# design.net
KiCad netlist of a schematic drawn in Altium Designer
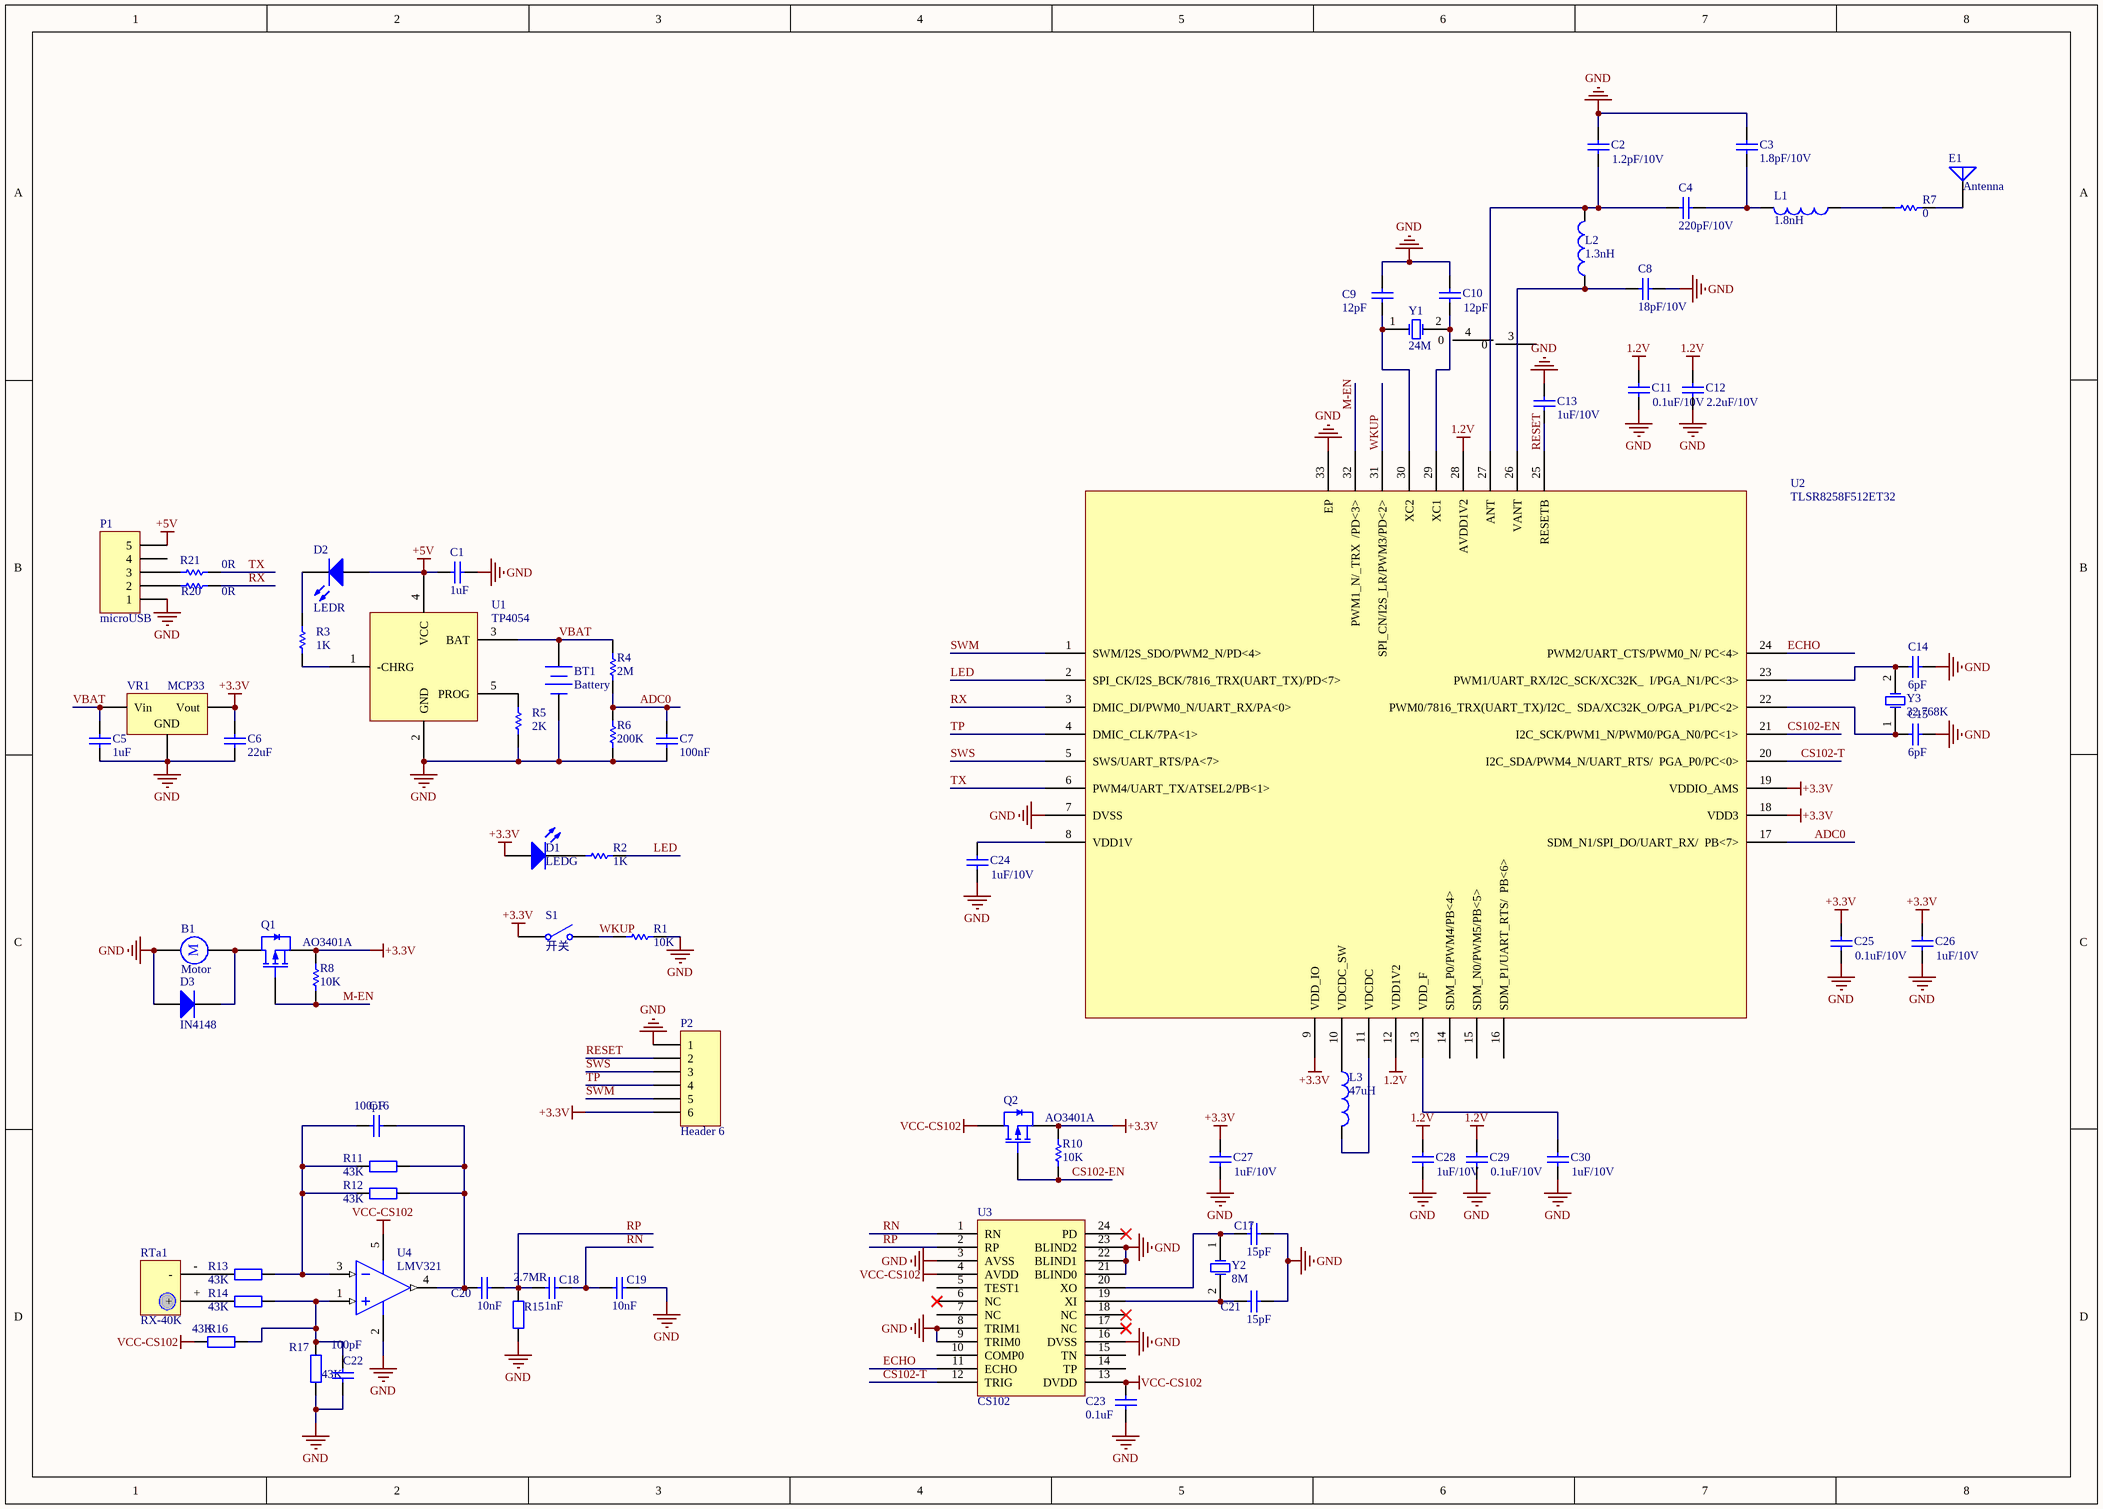
[diagram p0: 接收端原理图.SchDoc]

(export (version "E")
  (design (tool "Eeschema 10.0.6"))
  (components
    (comp (ref "B1")
      (value "Motor")
      (footprint "MOTO-40*44*114 - 3D")
      (description "Motor, General Kind")
      (fields (field (name "PUBLISHER") "Altium Limited"))
      (libsource (lib "Miscellaneous Devices") (part "Motor"))
    )
    (comp (ref "BT1")
      (value "Battery")
      (footprint "BT")
      (description "Multicell Battery")
      (fields (field (name "PUBLISHER") "Altium Limited"))
      (libsource (lib "Miscellaneous Devices") (part "Battery"))
    )
    (comp (ref "C1")
      (value "1uF")
      (description "Capacitor")
      (fields (field (name "PUBLISHER") "Altium Limited"))
      (libsource (lib "Miscellaneous Devices") (part "Cap"))
    )
    (comp (ref "C2")
      (value "1.2pF/10V")
      (footprint "0402")
      (description "Capacitor")
      (fields (field (name "PUBLISHER") "Altium Limited"))
      (libsource (lib "Miscellaneous Devices") (part "Cap"))
    )
    (comp (ref "C3")
      (value "1.8pF/10V")
      (footprint "0402")
      (description "Capacitor")
      (fields (field (name "PUBLISHER") "Altium Limited"))
      (libsource (lib "Miscellaneous Devices") (part "Cap"))
    )
    (comp (ref "C4")
      (value "220pF/10V")
      (footprint "0402")
      (description "Capacitor")
      (fields (field (name "PUBLISHER") "Altium Limited"))
      (libsource (lib "Miscellaneous Devices") (part "Cap"))
    )
    (comp (ref "C5")
      (value "1uF")
      (description "Capacitor")
      (fields (field (name "PUBLISHER") "Altium Limited"))
      (libsource (lib "Miscellaneous Devices") (part "Cap"))
    )
    (comp (ref "C6")
      (value "22uF")
      (description "Capacitor")
      (fields (field (name "PUBLISHER") "Altium Limited"))
      (libsource (lib "Miscellaneous Devices") (part "Cap"))
    )
    (comp (ref "C7")
      (value "100nF")
      (description "Capacitor")
      (fields (field (name "PUBLISHER") "Altium Limited"))
      (libsource (lib "Miscellaneous Devices") (part "Cap"))
    )
    (comp (ref "C8")
      (value "18pF/10V")
      (footprint "0402")
      (description "Capacitor")
      (fields (field (name "PUBLISHER") "Altium Limited"))
      (libsource (lib "Miscellaneous Devices") (part "Cap"))
    )
    (comp (ref "C9")
      (value "12pF")
      (footprint "0402")
      (description "Capacitor")
      (fields (field (name "PUBLISHER") "Altium Limited"))
      (libsource (lib "Miscellaneous Devices") (part "Cap"))
    )
    (comp (ref "C10")
      (value "12pF")
      (footprint "0402")
      (description "Capacitor")
      (fields (field (name "PUBLISHER") "Altium Limited"))
      (libsource (lib "Miscellaneous Devices") (part "Cap"))
    )
    (comp (ref "C11")
      (value "0.1uF/10V")
      (footprint "0402")
      (description "Capacitor")
      (fields (field (name "PUBLISHER") "Altium Limited"))
      (libsource (lib "Miscellaneous Devices") (part "Cap"))
    )
    (comp (ref "C12")
      (value "2.2uF/10V")
      (footprint "0402")
      (description "Capacitor")
      (fields (field (name "PUBLISHER") "Altium Limited"))
      (libsource (lib "Miscellaneous Devices") (part "Cap"))
    )
    (comp (ref "C13")
      (value "1uF/10V")
      (footprint "0402")
      (description "Capacitor")
      (fields (field (name "PUBLISHER") "Altium Limited"))
      (libsource (lib "Miscellaneous Devices") (part "Cap"))
    )
    (comp (ref "C14")
      (value "6pF")
      (footprint "0402")
      (description "Capacitor")
      (fields (field (name "PUBLISHER") "Altium Limited"))
      (libsource (lib "Miscellaneous Devices") (part "Cap"))
    )
    (comp (ref "C15")
      (value "6pF")
      (footprint "0402")
      (description "Capacitor")
      (fields (field (name "PUBLISHER") "Altium Limited"))
      (libsource (lib "Miscellaneous Devices") (part "Cap"))
    )
    (comp (ref "C16")
      (value "100pF")
      (footprint "0402")
      (description "Capacitor")
      (fields (field (name "PUBLISHER") "Altium Limited"))
      (libsource (lib "Miscellaneous Devices") (part "Cap"))
    )
    (comp (ref "C17")
      (value "15pF")
      (footprint "0402")
      (description "Capacitor")
      (fields (field (name "PUBLISHER") "Altium Limited"))
      (libsource (lib "Miscellaneous Devices") (part "Cap"))
    )
    (comp (ref "C18")
      (value "1nF")
      (footprint "0402")
      (description "Capacitor")
      (fields (field (name "PUBLISHER") "Altium Limited"))
      (libsource (lib "Miscellaneous Devices") (part "Cap"))
    )
    (comp (ref "C19")
      (value "10nF")
      (footprint "0402")
      (description "Capacitor")
      (fields (field (name "PUBLISHER") "Altium Limited"))
      (libsource (lib "Miscellaneous Devices") (part "Cap"))
    )
    (comp (ref "C20")
      (value "10nF")
      (footprint "0402")
      (description "Capacitor")
      (fields (field (name "PUBLISHER") "Altium Limited"))
      (libsource (lib "Miscellaneous Devices") (part "Cap"))
    )
    (comp (ref "C21")
      (value "15pF")
      (footprint "0402")
      (description "Capacitor")
      (fields (field (name "PUBLISHER") "Altium Limited"))
      (libsource (lib "Miscellaneous Devices") (part "Cap"))
    )
    (comp (ref "C22")
      (value "100pF")
      (footprint "0402")
      (description "Capacitor")
      (fields (field (name "PUBLISHER") "Altium Limited"))
      (libsource (lib "Miscellaneous Devices") (part "Cap"))
    )
    (comp (ref "C23")
      (value "0.1uF")
      (description "Capacitor")
      (fields (field (name "PUBLISHER") "Altium Limited"))
      (libsource (lib "Miscellaneous Devices") (part "Cap"))
    )
    (comp (ref "C24")
      (value "1uF/10V")
      (footprint "0402")
      (description "Capacitor")
      (fields (field (name "PUBLISHER") "Altium Limited"))
      (libsource (lib "Miscellaneous Devices") (part "Cap"))
    )
    (comp (ref "C25")
      (value "0.1uF/10V")
      (footprint "0402")
      (description "Capacitor")
      (fields (field (name "PUBLISHER") "Altium Limited"))
      (libsource (lib "Miscellaneous Devices") (part "Cap"))
    )
    (comp (ref "C26")
      (value "1uF/10V")
      (footprint "0402")
      (description "Capacitor")
      (fields (field (name "PUBLISHER") "Altium Limited"))
      (libsource (lib "Miscellaneous Devices") (part "Cap"))
    )
    (comp (ref "C27")
      (value "1uF/10V")
      (footprint "0402")
      (description "Capacitor")
      (fields (field (name "PUBLISHER") "Altium Limited"))
      (libsource (lib "Miscellaneous Devices") (part "Cap"))
    )
    (comp (ref "C28")
      (value "1uF/10V")
      (footprint "0402")
      (description "Capacitor")
      (fields (field (name "PUBLISHER") "Altium Limited"))
      (libsource (lib "Miscellaneous Devices") (part "Cap"))
    )
    (comp (ref "C29")
      (value "0.1uF/10V")
      (footprint "0402")
      (description "Capacitor")
      (fields (field (name "PUBLISHER") "Altium Limited"))
      (libsource (lib "Miscellaneous Devices") (part "Cap"))
    )
    (comp (ref "C30")
      (value "1uF/10V")
      (footprint "0402")
      (description "Capacitor")
      (fields (field (name "PUBLISHER") "Altium Limited"))
      (libsource (lib "Miscellaneous Devices") (part "Cap"))
    )
    (comp (ref "D1")
      (value "LEDG")
      (footprint "LED0603")
      (description "Typical INFRARED GaAs LED")
      (fields (field (name "PUBLISHER") "Altium Limited"))
      (libsource (lib "Miscellaneous Devices") (part "LED0"))
    )
    (comp (ref "D2")
      (value "LEDR")
      (footprint "LED0603")
      (description "Typical INFRARED GaAs LED")
      (fields (field (name "PUBLISHER") "Altium Limited"))
      (libsource (lib "Miscellaneous Devices") (part "LED0"))
    )
    (comp (ref "D3")
      (value "IN4148")
      (footprint "LED0603")
      (description "Default Diode")
      (fields (field (name "PUBLISHER") "Altium Limited"))
      (libsource (lib "Miscellaneous Devices") (part "Diode"))
    )
    (comp (ref "E1")
      (value "Antenna")
      (footprint "AN3216")
      (description "Generic Antenna")
      (fields (field (name "PUBLISHER") "Altium Limited"))
      (libsource (lib "Miscellaneous Devices") (part "Antenna"))
    )
    (comp (ref "L1")
      (value "1.8nH")
      (description "Inductor")
      (fields (field (name "PUBLISHER") "Altium Limited"))
      (libsource (lib "Miscellaneous Devices") (part "Inductor"))
    )
    (comp (ref "L2")
      (value "1.3nH")
      (description "Inductor")
      (fields (field (name "PUBLISHER") "Altium Limited"))
      (libsource (lib "Miscellaneous Devices") (part "Inductor"))
    )
    (comp (ref "L3")
      (value "47uH")
      (description "Inductor")
      (fields (field (name "PUBLISHER") "Altium Limited"))
      (libsource (lib "Miscellaneous Devices") (part "Inductor"))
    )
    (comp (ref "P1")
      (value "microUSB")
      (footprint "MICROUSB")
      (description "Header, 5-Pin")
      (fields (field (name "PUBLISHER") "Altium Limited"))
      (libsource (lib "Miscellaneous Connectors") (part "Header 5"))
    )
    (comp (ref "P2")
      (value "Header 6")
      (footprint "SIP6-1.27")
      (description "Header, 6-Pin")
      (fields (field (name "PUBLISHER") "Altium Limited"))
      (libsource (lib "Miscellaneous Connectors") (part "Header 6"))
    )
    (comp (ref "Q1")
      (value "AO3401A")
      (footprint "AO3401")
      (description "MOS(场效应管)")
      (libsource (lib "Miscellaneous Devices LC") (part "AO3401A P道沟 X13A15 SOT-23"))
    )
    (comp (ref "Q2")
      (value "AO3401A")
      (footprint "AO3401")
      (description "MOS(场效应管)")
      (libsource (lib "Miscellaneous Devices LC") (part "AO3401A P道沟 X13A15 SOT-23"))
    )
    (comp (ref "R1")
      (value "10K")
      (description "Resistor")
      (fields (field (name "PUBLISHER") "Altium Limited"))
      (libsource (lib "Miscellaneous Devices") (part "Res1"))
    )
    (comp (ref "R2")
      (value "1K")
      (description "Resistor")
      (fields (field (name "PUBLISHER") "Altium Limited"))
      (libsource (lib "Miscellaneous Devices") (part "Res1"))
    )
    (comp (ref "R3")
      (value "1K")
      (description "Resistor")
      (fields (field (name "PUBLISHER") "Altium Limited"))
      (libsource (lib "Miscellaneous Devices") (part "Res1"))
    )
    (comp (ref "R4")
      (value "2M")
      (description "Resistor")
      (fields (field (name "PUBLISHER") "Altium Limited"))
      (libsource (lib "Miscellaneous Devices") (part "Res1"))
    )
    (comp (ref "R5")
      (value "2K")
      (description "Resistor")
      (fields (field (name "PUBLISHER") "Altium Limited"))
      (libsource (lib "Miscellaneous Devices") (part "Res1"))
    )
    (comp (ref "R6")
      (value "200K")
      (description "Resistor")
      (fields (field (name "PUBLISHER") "Altium Limited"))
      (libsource (lib "Miscellaneous Devices") (part "Res1"))
    )
    (comp (ref "R7")
      (value "0")
      (description "Resistor")
      (fields (field (name "PUBLISHER") "Altium Limited"))
      (libsource (lib "Miscellaneous Devices") (part "Res1"))
    )
    (comp (ref "R8")
      (value "10K")
      (description "Resistor")
      (fields (field (name "PUBLISHER") "Altium Limited"))
      (libsource (lib "Miscellaneous Devices") (part "Res1"))
    )
    (comp (ref "R10")
      (value "10K")
      (description "Resistor")
      (fields (field (name "PUBLISHER") "Altium Limited"))
      (libsource (lib "Miscellaneous Devices") (part "Res1"))
    )
    (comp (ref "R11")
      (value "43K")
      (footprint "0402")
      (description "Resistor")
      (fields (field (name "PUBLISHER") "Altium Limited"))
      (libsource (lib "") (part "Res2_2"))
    )
    (comp (ref "R12")
      (value "43K")
      (footprint "0402")
      (description "Resistor")
      (fields (field (name "PUBLISHER") "Altium Limited"))
      (libsource (lib "") (part "Res2_2"))
    )
    (comp (ref "R13")
      (value "43K")
      (footprint "0402")
      (description "Resistor")
      (fields (field (name "PUBLISHER") "Altium Limited"))
      (libsource (lib "") (part "Res2_2"))
    )
    (comp (ref "R14")
      (value "43K")
      (footprint "0402")
      (description "Resistor")
      (fields (field (name "PUBLISHER") "Altium Limited"))
      (libsource (lib "") (part "Res2_2"))
    )
    (comp (ref "R15")
      (value "2.7MR")
      (footprint "0402")
      (description "Resistor")
      (fields (field (name "PUBLISHER") "Altium Limited"))
      (libsource (lib "Miscellaneous Devices") (part "Res2"))
    )
    (comp (ref "R16")
      (value "43K")
      (footprint "0402")
      (description "Resistor")
      (fields (field (name "PUBLISHER") "Altium Limited"))
      (libsource (lib "") (part "Res2_1"))
    )
    (comp (ref "R17")
      (value "43K")
      (footprint "0402")
      (description "Resistor")
      (fields (field (name "PUBLISHER") "Altium Limited"))
      (libsource (lib "Miscellaneous Devices") (part "Res2"))
    )
    (comp (ref "R20")
      (value "0R")
      (description "Resistor")
      (fields (field (name "PUBLISHER") "Altium Limited"))
      (libsource (lib "Miscellaneous Devices") (part "Res1"))
    )
    (comp (ref "R21")
      (value "0R")
      (description "Resistor")
      (fields (field (name "PUBLISHER") "Altium Limited"))
      (libsource (lib "Miscellaneous Devices") (part "Res1"))
    )
    (comp (ref "RTa1") (value "RX-40K") (footprint "US-10mm") (libsource (lib "USLib") (part "TC40K")))
    (comp (ref "S1")
      (value "开关")
      (footprint "SW3x6x5")
      (description "Single-Pole, Single-Throw Switch")
      (fields (field (name "PUBLISHER") "Altium Limited"))
      (libsource (lib "Miscellaneous Devices") (part "SW-SPST"))
    )
    (comp (ref "U1") (value "TP4054") (footprint "TP4054") (libsource (lib "Schlib1") (part "TP4054")))
    (comp (ref "U2")
      (value "TLSR8258F512ET32")
      (footprint "QFN-32")
      (libsource (lib "stm32") (part "TLSR8258F512ET32"))
    )
    (comp (ref "U3") (value "CS102") (footprint "TSSOP24") (libsource (lib "USLib") (part "CS100")))
    (comp (ref "U4")
      (value "LMV321")
      (footprint "MF05A_N")
      (description "General Purpose, Low Voltage, Rail-to-Rail Output Operational Amplifiers")
      (fields
        (field (name "PARTNUMBER") "LMV321M5")
        (field (name "MANUFACTURER") "National Semiconductor")
        (field (name "PUBLISHER") "Altium Limited")
      )
      (libsource (lib "NSC Amplifier") (part "LMV321M5"))
    )
    (comp (ref "VR1")
      (value "MCP33")
      (footprint "MCP33")
      (description "Voltage Regulator")
      (fields (field (name "PUBLISHER") "Altium Limited"))
      (libsource (lib "Miscellaneous Devices") (part "Volt Reg"))
    )
    (comp (ref "Y1")
      (value "24M")
      (footprint "XTAL4TN_3225")
      (description "Crystal Oscillator")
      (fields (field (name "PUBLISHER") "Altium Limited"))
      (libsource (lib "") (part "XTAL_1"))
    )
    (comp (ref "Y2")
      (value "8M")
      (footprint "5032")
      (description "Crystal Oscillator")
      (fields (field (name "PUBLISHER") "Altium Limited"))
      (libsource (lib "Miscellaneous Devices") (part "XTAL"))
    )
    (comp (ref "Y3")
      (value "32.768K")
      (footprint "XTAL3215")
      (description "Crystal Oscillator")
      (fields (field (name "PUBLISHER") "Altium Limited"))
      (libsource (lib "Miscellaneous Devices") (part "XTAL"))
    )
  )
  (nets
    (net (code "1") (name "+3.3V") (class "Default")
      (node (ref "C25") (pin "2") (pinfunction "2_2") (pintype "passive"))
      (node (ref "C26") (pin "2") (pinfunction "2_2") (pintype "passive"))
      (node (ref "C27") (pin "2") (pinfunction "2_2") (pintype "passive"))
      (node (ref "C6") (pin "1") (pinfunction "1_1") (pintype "passive"))
      (node (ref "D1") (pin "1") (pinfunction "A_1") (pintype "passive"))
      (node (ref "P2") (pin "6") (pinfunction "6_6") (pintype "passive"))
      (node (ref "Q1") (pin "2") (pinfunction "S_2") (pintype "passive"))
      (node (ref "Q2") (pin "2") (pinfunction "S_2") (pintype "passive"))
      (node (ref "R10") (pin "2") (pinfunction "2_2") (pintype "passive"))
      (node (ref "R8") (pin "2") (pinfunction "2_2") (pintype "passive"))
      (node (ref "S1") (pin "1") (pinfunction "COMMON_1") (pintype "passive"))
      (node (ref "U2") (pin "18") (pinfunction "VDD3_18") (pintype "passive"))
      (node (ref "U2") (pin "19") (pinfunction "VDDIO_AMS_19") (pintype "passive"))
      (node (ref "U2") (pin "9") (pinfunction "VDD_IO_9") (pintype "passive"))
      (node (ref "VR1") (pin "3") (pinfunction "Vout_3") (pintype "passive"))
    )
    (net (code "2") (name "+5V") (class "Default")
      (node (ref "C1") (pin "2") (pinfunction "2_2") (pintype "passive"))
      (node (ref "D2") (pin "1") (pinfunction "A_1") (pintype "passive"))
      (node (ref "P1") (pin "5") (pinfunction "5_5") (pintype "passive"))
      (node (ref "U1") (pin "4") (pinfunction "VCC_4") (pintype "passive"))
    )
    (net (code "3") (name "/ADC0") (class "Default")
      (node (ref "C7") (pin "2") (pinfunction "2_2") (pintype "passive"))
      (node (ref "R4") (pin "1") (pinfunction "1_1") (pintype "passive"))
      (node (ref "R6") (pin "2") (pinfunction "2_2") (pintype "passive"))
      (node (ref "U2") (pin "17") (pinfunction "SDM_N1/SPI_DO/UART_RX/__PB<7>_17") (pintype "passive"))
    )
    (net (code "4") (name "/CS102-EN") (class "Default")
      (node (ref "Q2") (pin "1") (pinfunction "G_1") (pintype "passive"))
      (node (ref "R10") (pin "1") (pinfunction "1_1") (pintype "passive"))
      (node (ref "U2") (pin "21") (pinfunction "I2C_SCK/PWM1_N/PWM0/PGA_N0/PC<1>_21") (pintype "passive"))
    )
    (net (code "5") (name "/CS102-T") (class "Default")
      (node (ref "U2") (pin "20") (pinfunction "I2C_SDA/PWM4_N/UART_RTS/__PGA_P0/PC<0>_20") (pintype "passive"))
      (node (ref "U3") (pin "12") (pinfunction "TRIG_12") (pintype "passive"))
    )
    (net (code "6") (name "/ECHO") (class "Default")
      (node (ref "U2") (pin "24") (pinfunction "PWM2/UART_CTS/PWM0_N/_PC<4>_24") (pintype "passive"))
      (node (ref "U3") (pin "11") (pinfunction "ECHO_11") (pintype "passive"))
    )
    (net (code "7") (name "/LED") (class "Default")
      (node (ref "R2") (pin "1") (pinfunction "1_1") (pintype "passive"))
      (node (ref "U2") (pin "2") (pinfunction "SPI_CK/I2S_BCK/7816_TRX(UART_TX)/PD<7>_2") (pintype "passive"))
    )
    (net (code "8") (name "/M-EN") (class "Default")
      (node (ref "Q1") (pin "1") (pinfunction "G_1") (pintype "passive"))
      (node (ref "R8") (pin "1") (pinfunction "1_1") (pintype "passive"))
      (node (ref "U2") (pin "32") (pinfunction "PWM1_N/_TRX__/PD<3>_32") (pintype "passive"))
    )
    (net (code "9") (name "/RESET") (class "Default")
      (node (ref "C13") (pin "2") (pinfunction "2_2") (pintype "passive"))
      (node (ref "P2") (pin "2") (pinfunction "2_2") (pintype "passive"))
      (node (ref "U2") (pin "25") (pinfunction "RESETB_25") (pintype "passive"))
    )
    (net (code "10") (name "/RN") (class "Default")
      (node (ref "C18") (pin "2") (pinfunction "2_2") (pintype "passive"))
      (node (ref "C19") (pin "1") (pinfunction "1_1") (pintype "passive"))
      (node (ref "U3") (pin "1") (pinfunction "RN_1") (pintype "passive"))
    )
    (net (code "11") (name "/RP") (class "Default")
      (node (ref "C18") (pin "1") (pinfunction "1_1") (pintype "passive"))
      (node (ref "C20") (pin "2") (pinfunction "2_2") (pintype "passive"))
      (node (ref "R15") (pin "2") (pinfunction "2_2") (pintype "passive"))
      (node (ref "U3") (pin "2") (pinfunction "RP_2") (pintype "passive"))
    )
    (net (code "12") (name "/RX") (class "Default")
      (node (ref "R20") (pin "1") (pinfunction "1_1") (pintype "passive"))
      (node (ref "U2") (pin "3") (pinfunction "DMIC_DI/PWM0_N/UART_RX/PA<0>_3") (pintype "passive"))
    )
    (net (code "13") (name "/SWM") (class "Default")
      (node (ref "P2") (pin "5") (pinfunction "5_5") (pintype "passive"))
      (node (ref "U2") (pin "1") (pinfunction "SWM/I2S_SDO/PWM2_N/PD<4>_1") (pintype "passive"))
    )
    (net (code "14") (name "/SWS") (class "Default")
      (node (ref "P2") (pin "3") (pinfunction "3_3") (pintype "passive"))
      (node (ref "U2") (pin "5") (pinfunction "SWS/UART_RTS/PA<7>_5") (pintype "passive"))
    )
    (net (code "15") (name "/TP") (class "Default")
      (node (ref "P2") (pin "4") (pinfunction "4_4") (pintype "passive"))
      (node (ref "U2") (pin "4") (pinfunction "DMIC_CLK/7PA<1>_4") (pintype "passive"))
    )
    (net (code "16") (name "/TX") (class "Default")
      (node (ref "R21") (pin "1") (pinfunction "1_1") (pintype "passive"))
      (node (ref "U2") (pin "6") (pinfunction "PWM4/UART_TX/ATSEL2/PB<1>_6") (pintype "passive"))
    )
    (net (code "17") (name "/VBAT") (class "Default")
      (node (ref "BT1") (pin "1") (pinfunction "+_1") (pintype "passive"))
      (node (ref "C5") (pin "1") (pinfunction "1_1") (pintype "passive"))
      (node (ref "R4") (pin "2") (pinfunction "2_2") (pintype "passive"))
      (node (ref "U1") (pin "3") (pinfunction "BAT_3") (pintype "passive"))
      (node (ref "VR1") (pin "1") (pinfunction "Vin_1") (pintype "passive"))
    )
    (net (code "18") (name "/WKUP") (class "Default")
      (node (ref "R1") (pin "2") (pinfunction "2_2") (pintype "passive"))
      (node (ref "S1") (pin "2") (pinfunction "NO_2") (pintype "passive"))
      (node (ref "U2") (pin "31") (pinfunction "SPI_CN/I2S_LR/PWM3/PD<2>_31") (pintype "passive"))
    )
    (net (code "19") (name "1.2V") (class "Default")
      (node (ref "C11") (pin "2") (pinfunction "2_2") (pintype "passive"))
      (node (ref "C12") (pin "2") (pinfunction "2_2") (pintype "passive"))
      (node (ref "C28") (pin "2") (pinfunction "2_2") (pintype "passive"))
      (node (ref "C29") (pin "2") (pinfunction "2_2") (pintype "passive"))
      (node (ref "U2") (pin "12") (pinfunction "VDD1V2_12") (pintype "passive"))
      (node (ref "U2") (pin "28") (pinfunction "AVDD1V2_28") (pintype "passive"))
    )
    (net (code "20") (name "GND") (class "Default")
      (node (ref "B1") (pin "1") (pinfunction "1_1") (pintype "passive"))
      (node (ref "BT1") (pin "2") (pinfunction "-_2") (pintype "passive"))
      (node (ref "C1") (pin "1") (pinfunction "1_1") (pintype "passive"))
      (node (ref "C10") (pin "2") (pinfunction "2_2") (pintype "passive"))
      (node (ref "C11") (pin "1") (pinfunction "1_1") (pintype "passive"))
      (node (ref "C12") (pin "1") (pinfunction "1_1") (pintype "passive"))
      (node (ref "C13") (pin "1") (pinfunction "1_1") (pintype "passive"))
      (node (ref "C14") (pin "1") (pinfunction "1_1") (pintype "passive"))
      (node (ref "C15") (pin "1") (pinfunction "1_1") (pintype "passive"))
      (node (ref "C17") (pin "2") (pinfunction "2_2") (pintype "passive"))
      (node (ref "C19") (pin "2") (pinfunction "2_2") (pintype "passive"))
      (node (ref "C2") (pin "2") (pinfunction "2_2") (pintype "passive"))
      (node (ref "C21") (pin "2") (pinfunction "2_2") (pintype "passive"))
      (node (ref "C22") (pin "1") (pinfunction "1_1") (pintype "passive"))
      (node (ref "C23") (pin "1") (pinfunction "1_1") (pintype "passive"))
      (node (ref "C24") (pin "1") (pinfunction "1_1") (pintype "passive"))
      (node (ref "C25") (pin "1") (pinfunction "1_1") (pintype "passive"))
      (node (ref "C26") (pin "1") (pinfunction "1_1") (pintype "passive"))
      (node (ref "C27") (pin "1") (pinfunction "1_1") (pintype "passive"))
      (node (ref "C28") (pin "1") (pinfunction "1_1") (pintype "passive"))
      (node (ref "C29") (pin "1") (pinfunction "1_1") (pintype "passive"))
      (node (ref "C3") (pin "1") (pinfunction "1_1") (pintype "passive"))
      (node (ref "C30") (pin "1") (pinfunction "1_1") (pintype "passive"))
      (node (ref "C5") (pin "2") (pinfunction "2_2") (pintype "passive"))
      (node (ref "C6") (pin "2") (pinfunction "2_2") (pintype "passive"))
      (node (ref "C7") (pin "1") (pinfunction "1_1") (pintype "passive"))
      (node (ref "C8") (pin "1") (pinfunction "1_1") (pintype "passive"))
      (node (ref "C9") (pin "2") (pinfunction "2_2") (pintype "passive"))
      (node (ref "D3") (pin "1") (pinfunction "A_1") (pintype "passive"))
      (node (ref "P1") (pin "1") (pinfunction "1_1") (pintype "passive"))
      (node (ref "P2") (pin "1") (pinfunction "1_1") (pintype "passive"))
      (node (ref "R1") (pin "1") (pinfunction "1_1") (pintype "passive"))
      (node (ref "R15") (pin "1") (pinfunction "1_1") (pintype "passive"))
      (node (ref "R17") (pin "1") (pinfunction "1_1") (pintype "passive"))
      (node (ref "R5") (pin "1") (pinfunction "1_1") (pintype "passive"))
      (node (ref "R6") (pin "1") (pinfunction "1_1") (pintype "passive"))
      (node (ref "U1") (pin "2") (pinfunction "GND_2") (pintype "passive"))
      (node (ref "U2") (pin "33") (pinfunction "EP_33") (pintype "passive"))
      (node (ref "U2") (pin "7") (pinfunction "DVSS_7") (pintype "passive"))
      (node (ref "U3") (pin "16") (pinfunction "DVSS_16") (pintype "passive"))
      (node (ref "U3") (pin "21") (pinfunction "BLIND0_21") (pintype "passive"))
      (node (ref "U3") (pin "22") (pinfunction "BLIND1_22") (pintype "passive"))
      (node (ref "U3") (pin "23") (pinfunction "BLIND2_23") (pintype "passive"))
      (node (ref "U3") (pin "3") (pinfunction "AVSS_3") (pintype "passive"))
      (node (ref "U3") (pin "8") (pinfunction "TRIM1_8") (pintype "passive"))
      (node (ref "U3") (pin "9") (pinfunction "TRIM0_9") (pintype "passive"))
      (node (ref "U4") (pin "2") (pinfunction "V-_2") (pintype "power_in"))
      (node (ref "VR1") (pin "2") (pinfunction "GND_2") (pintype "passive"))
    )
    (net (code "21") (name "Net-(C3-Pad2)") (class "Default")
      (node (ref "C3") (pin "2") (pinfunction "2_2") (pintype "passive"))
      (node (ref "C4") (pin "1") (pinfunction "1_1") (pintype "passive"))
      (node (ref "L1") (pin "2") (pinfunction "2_2") (pintype "passive"))
    )
    (net (code "22") (name "Net-(D1-K)") (class "Default")
      (node (ref "D1") (pin "2") (pinfunction "K_2") (pintype "passive"))
      (node (ref "R2") (pin "2") (pinfunction "2_2") (pintype "passive"))
    )
    (net (code "23") (name "Net-(D2-K)") (class "Default")
      (node (ref "D2") (pin "2") (pinfunction "K_2") (pintype "passive"))
      (node (ref "R3") (pin "2") (pinfunction "2_2") (pintype "passive"))
    )
    (net (code "24") (name "Net-(D3-K)") (class "Default")
      (node (ref "B1") (pin "2") (pinfunction "2_2") (pintype "passive"))
      (node (ref "D3") (pin "2") (pinfunction "K_2") (pintype "passive"))
      (node (ref "Q1") (pin "3") (pinfunction "D_3") (pintype "passive"))
    )
    (net (code "25") (name "Net-(E1-A)") (class "Default")
      (node (ref "E1") (pin "1") (pinfunction "A_1") (pintype "passive"))
      (node (ref "R7") (pin "1") (pinfunction "1_1") (pintype "passive"))
    )
    (net (code "26") (name "Net-(L1-Pad1)") (class "Default")
      (node (ref "L1") (pin "1") (pinfunction "1_1") (pintype "passive"))
      (node (ref "R7") (pin "2") (pinfunction "2_2") (pintype "passive"))
    )
    (net (code "27") (name "Net-(P1-Pad2)") (class "Default")
      (node (ref "P1") (pin "2") (pinfunction "2_2") (pintype "passive"))
      (node (ref "R20") (pin "2") (pinfunction "2_2") (pintype "passive"))
    )
    (net (code "28") (name "Net-(P1-Pad3)") (class "Default")
      (node (ref "P1") (pin "3") (pinfunction "3_3") (pintype "passive"))
      (node (ref "R21") (pin "2") (pinfunction "2_2") (pintype "passive"))
    )
    (net (code "29") (name "Net-(R13-Pad1)") (class "Default")
      (node (ref "R13") (pin "1") (pinfunction "1_1") (pintype "passive"))
      (node (ref "RTa1") (pin "-") (pinfunction "-_-") (pintype "passive"))
    )
    (net (code "30") (name "Net-(R14-Pad1)") (class "Default")
      (node (ref "R14") (pin "1") (pinfunction "1_1") (pintype "passive"))
      (node (ref "RTa1") (pin "+") (pinfunction "+_+") (pintype "passive"))
    )
    (net (code "31") (name "Net-(U1--CHRG)") (class "Default")
      (node (ref "R3") (pin "1") (pinfunction "1_1") (pintype "passive"))
      (node (ref "U1") (pin "1") (pinfunction "-CHRG_1") (pintype "passive"))
    )
    (net (code "32") (name "Net-(U1-PROG)") (class "Default")
      (node (ref "R5") (pin "2") (pinfunction "2_2") (pintype "passive"))
      (node (ref "U1") (pin "5") (pinfunction "PROG_5") (pintype "passive"))
    )
    (net (code "33") (name "Net-(U2-ANT)") (class "Default")
      (node (ref "C2") (pin "1") (pinfunction "1_1") (pintype "passive"))
      (node (ref "C4") (pin "2") (pinfunction "2_2") (pintype "passive"))
      (node (ref "L2") (pin "2") (pinfunction "2_2") (pintype "passive"))
      (node (ref "U2") (pin "27") (pinfunction "ANT_27") (pintype "passive"))
    )
    (net (code "34") (name "Net-(U2-PWM0{slash}7816_TRX(UART_TX){slash}I2C___SDA{slash}XC32K_O{slash}PGA_P1{slash}PC<2>)") (class "Default")
      (node (ref "C15") (pin "2") (pinfunction "2_2") (pintype "passive"))
      (node (ref "U2") (pin "22") (pinfunction "PWM0/7816_TRX(UART_TX)/I2C___SDA/XC32K_O/PGA_P1/PC<2>_22") (pintype "passive"))
      (node (ref "Y3") (pin "1") (pinfunction "OSC1_1") (pintype "passive"))
    )
    (net (code "35") (name "Net-(U2-PWM1{slash}UART_RX{slash}I2C_SCK{slash}XC32K___I{slash}PGA_N1{slash}PC<3>)") (class "Default")
      (node (ref "C14") (pin "2") (pinfunction "2_2") (pintype "passive"))
      (node (ref "U2") (pin "23") (pinfunction "PWM1/UART_RX/I2C_SCK/XC32K___I/PGA_N1/PC<3>_23") (pintype "passive"))
      (node (ref "Y3") (pin "2") (pinfunction "OSC2_2") (pintype "passive"))
    )
    (net (code "36") (name "Net-(U2-VANT)") (class "Default")
      (node (ref "C8") (pin "2") (pinfunction "2_2") (pintype "passive"))
      (node (ref "L2") (pin "1") (pinfunction "1_1") (pintype "passive"))
      (node (ref "U2") (pin "26") (pinfunction "VANT_26") (pintype "passive"))
    )
    (net (code "37") (name "Net-(U2-VDCDC)") (class "Default")
      (node (ref "L3") (pin "2") (pinfunction "2_2") (pintype "passive"))
      (node (ref "U2") (pin "11") (pinfunction "VDCDC_11") (pintype "passive"))
    )
    (net (code "38") (name "Net-(U2-VDCDC_SW)") (class "Default")
      (node (ref "L3") (pin "1") (pinfunction "1_1") (pintype "passive"))
      (node (ref "U2") (pin "10") (pinfunction "VDCDC_SW_10") (pintype "passive"))
    )
    (net (code "39") (name "Net-(U2-VDD1V)") (class "Default")
      (node (ref "C24") (pin "2") (pinfunction "2_2") (pintype "passive"))
      (node (ref "U2") (pin "8") (pinfunction "VDD1V_8") (pintype "passive"))
    )
    (net (code "40") (name "Net-(U2-VDD_F)") (class "Default")
      (node (ref "C30") (pin "2") (pinfunction "2_2") (pintype "passive"))
      (node (ref "U2") (pin "13") (pinfunction "VDD_F_13") (pintype "passive"))
    )
    (net (code "41") (name "Net-(U2-XC1)") (class "Default")
      (node (ref "C10") (pin "1") (pinfunction "1_1") (pintype "passive"))
      (node (ref "U2") (pin "29") (pinfunction "XC1_29") (pintype "passive"))
      (node (ref "Y1") (pin "2") (pinfunction "OSC2_2") (pintype "passive"))
    )
    (net (code "42") (name "Net-(U2-XC2)") (class "Default")
      (node (ref "C9") (pin "1") (pinfunction "1_1") (pintype "passive"))
      (node (ref "U2") (pin "30") (pinfunction "XC2_30") (pintype "passive"))
      (node (ref "Y1") (pin "1") (pinfunction "OSC1_1") (pintype "passive"))
    )
    (net (code "43") (name "Net-(U3-XI)") (class "Default")
      (node (ref "C21") (pin "1") (pinfunction "1_1") (pintype "passive"))
      (node (ref "U3") (pin "19") (pinfunction "XI_19") (pintype "passive"))
      (node (ref "Y2") (pin "2") (pinfunction "OSC2_2") (pintype "passive"))
    )
    (net (code "44") (name "Net-(U3-XO)") (class "Default")
      (node (ref "C17") (pin "1") (pinfunction "1_1") (pintype "passive"))
      (node (ref "U3") (pin "20") (pinfunction "XO_20") (pintype "passive"))
      (node (ref "Y2") (pin "1") (pinfunction "OSC1_1") (pintype "passive"))
    )
    (net (code "45") (name "Net-(U4-IN+)") (class "Default")
      (node (ref "C22") (pin "2") (pinfunction "2_2") (pintype "passive"))
      (node (ref "R14") (pin "2") (pinfunction "2_2") (pintype "passive"))
      (node (ref "R16") (pin "1") (pinfunction "1_1") (pintype "passive"))
      (node (ref "R17") (pin "2") (pinfunction "2_2") (pintype "passive"))
      (node (ref "U4") (pin "1") (pinfunction "IN+_1") (pintype "input"))
    )
    (net (code "46") (name "Net-(U4-IN-)") (class "Default")
      (node (ref "C16") (pin "2") (pinfunction "2_2") (pintype "passive"))
      (node (ref "R11") (pin "1") (pinfunction "1_1") (pintype "passive"))
      (node (ref "R12") (pin "1") (pinfunction "1_1") (pintype "passive"))
      (node (ref "R13") (pin "2") (pinfunction "2_2") (pintype "passive"))
      (node (ref "U4") (pin "3") (pinfunction "IN-_3") (pintype "input"))
    )
    (net (code "47") (name "Net-(U4-OUT)") (class "Default")
      (node (ref "C16") (pin "1") (pinfunction "1_1") (pintype "passive"))
      (node (ref "C20") (pin "1") (pinfunction "1_1") (pintype "passive"))
      (node (ref "R11") (pin "2") (pinfunction "2_2") (pintype "passive"))
      (node (ref "R12") (pin "2") (pinfunction "2_2") (pintype "passive"))
      (node (ref "U4") (pin "4") (pinfunction "OUT_4") (pintype "output"))
    )
    (net (code "48") (name "VCC-CS102") (class "Default")
      (node (ref "C23") (pin "2") (pinfunction "2_2") (pintype "passive"))
      (node (ref "Q2") (pin "3") (pinfunction "D_3") (pintype "passive"))
      (node (ref "R16") (pin "2") (pinfunction "2_2") (pintype "passive"))
      (node (ref "U3") (pin "13") (pinfunction "DVDD_13") (pintype "passive"))
      (node (ref "U3") (pin "4") (pinfunction "AVDD_4") (pintype "passive"))
      (node (ref "U4") (pin "5") (pinfunction "V+_5") (pintype "power_in"))
    )
    (net (code "49") (name "unconnected-(P1-Pad4)") (class "Default")
      (node (ref "P1") (pin "4") (pinfunction "4_4") (pintype "passive"))
    )
    (net (code "50") (name "unconnected-(U2-SDM_N0{slash}PWM5{slash}PB<5>-Pad15)") (class "Default")
      (node (ref "U2") (pin "15") (pinfunction "SDM_N0/PWM5/PB<5>_15") (pintype "passive"))
    )
    (net (code "51") (name "unconnected-(U2-SDM_P0{slash}PWM4{slash}PB<4>-Pad14)") (class "Default")
      (node (ref "U2") (pin "14") (pinfunction "SDM_P0/PWM4/PB<4>_14") (pintype "passive"))
    )
    (net (code "52") (name "unconnected-(U2-SDM_P1{slash}UART_RTS{slash}__PB<6>-Pad16)") (class "Default")
      (node (ref "U2") (pin "16") (pinfunction "SDM_P1/UART_RTS/__PB<6>_16") (pintype "passive"))
    )
    (net (code "53") (name "unconnected-(U3-COMP0-Pad10)") (class "Default")
      (node (ref "U3") (pin "10") (pinfunction "COMP0_10") (pintype "passive"))
    )
    (net (code "54") (name "unconnected-(U3-NC-Pad6)") (class "Default")
      (node (ref "U3") (pin "6") (pinfunction "NC_6") (pintype "passive+no_connect"))
    )
    (net (code "55") (name "unconnected-(U3-NC-Pad7)") (class "Default")
      (node (ref "U3") (pin "7") (pinfunction "NC_7") (pintype "passive"))
    )
    (net (code "56") (name "unconnected-(U3-NC-Pad17)") (class "Default")
      (node (ref "U3") (pin "17") (pinfunction "NC_17") (pintype "passive+no_connect"))
    )
    (net (code "57") (name "unconnected-(U3-NC-Pad18)") (class "Default")
      (node (ref "U3") (pin "18") (pinfunction "NC_18") (pintype "passive+no_connect"))
    )
    (net (code "58") (name "unconnected-(U3-PD-Pad24)") (class "Default")
      (node (ref "U3") (pin "24") (pinfunction "PD_24") (pintype "passive+no_connect"))
    )
    (net (code "59") (name "unconnected-(U3-TEST1-Pad5)") (class "Default")
      (node (ref "U3") (pin "5") (pinfunction "TEST1_5") (pintype "passive"))
    )
    (net (code "60") (name "unconnected-(U3-TN-Pad15)") (class "Default")
      (node (ref "U3") (pin "15") (pinfunction "TN_15") (pintype "passive"))
    )
    (net (code "61") (name "unconnected-(U3-TP-Pad14)") (class "Default")
      (node (ref "U3") (pin "14") (pinfunction "TP_14") (pintype "passive"))
    )
    (net (code "62") (name "unconnected-(Y1-0-Pad3)") (class "Default")
      (node (ref "Y1") (pin "3") (pinfunction "0_3") (pintype "passive"))
    )
    (net (code "63") (name "unconnected-(Y1-0-Pad4)") (class "Default")
      (node (ref "Y1") (pin "4") (pinfunction "0_4") (pintype "passive"))
    )
  )
)
